# pitch_pause_led.net
KiCad netlist of a schematic drawn in EAGLE
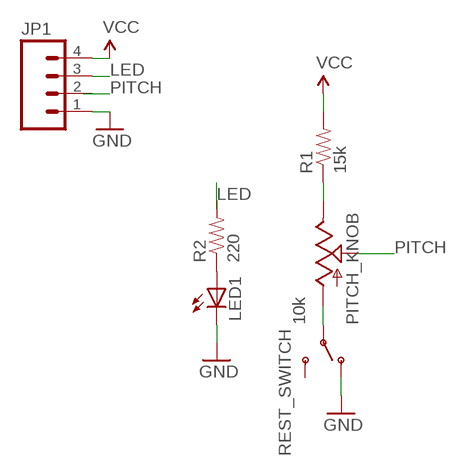
[diagram p0: schematic, sheet 1]

(export (version "E")
  (design (tool "Eeschema 10.0.6"))
  (components
    (comp (ref "JP1")
      (value "M04JST-PTH")
      (footprint "eagle-import:JST-4-PTH")
      (libsource (lib "eagle-import") (part "M04JST-PTH"))
    )
    (comp (ref "LED1")
      (value "LED-3MM-NO_SILK")
      (footprint "eagle-import:LED3MM-NS")
      (libsource (lib "eagle-import") (part "LED-3MM-NO_SILK"))
    )
    (comp (ref "PITCH_KNOB")
      (value "10k")
      (footprint "eagle-import:SPARKFUN_PDB12")
      (libsource (lib "eagle-import") (part "SPARKFUN_POTPDB12"))
    )
    (comp (ref "R1")
      (value "15k")
      (footprint "eagle-import:AXIAL-0.3")
      (libsource (lib "eagle-import") (part "RESISTORAXIAL-0.3"))
    )
    (comp (ref "R2")
      (value "220")
      (footprint "eagle-import:AXIAL-0.3")
      (libsource (lib "eagle-import") (part "RESISTORAXIAL-0.3"))
    )
    (comp (ref "REST_SWITCH")
      (value "SWITCH-SPDTPTH_LOCK")
      (footprint "eagle-import:SWITCH-SPDT_LOCK.007S")
      (libsource (lib "eagle-import") (part "SWITCH-SPDTPTH_LOCK"))
    )
  )
  (nets
    (net (code "1") (name "/LED") (class "Default")
      (node (ref "JP1") (pin "3") (pinfunction "3_3") (pintype "passive"))
      (node (ref "R2") (pin "P$2") (pinfunction "2_P$2") (pintype "passive"))
    )
    (net (code "2") (name "/PITCH") (class "Default")
      (node (ref "PITCH_KNOB") (pin "2") (pinfunction "S_2") (pintype "passive"))
    )
    (net (code "3") (name "GND") (class "Default")
      (node (ref "JP1") (pin "1") (pinfunction "1_1") (pintype "passive"))
      (node (ref "LED1") (pin "K") (pinfunction "C_K") (pintype "passive"))
      (node (ref "REST_SWITCH") (pin "1") (pinfunction "O_1") (pintype "passive"))
    )
    (net (code "4") (name "Net-(PITCH_KNOB-A)") (class "Default")
      (node (ref "PITCH_KNOB") (pin "1") (pinfunction "A_1") (pintype "passive"))
      (node (ref "REST_SWITCH") (pin "2") (pinfunction "P_2") (pintype "passive"))
    )
    (net (code "5") (name "Net-(PITCH_KNOB-E)") (class "Default")
      (node (ref "PITCH_KNOB") (pin "3") (pinfunction "E_3") (pintype "passive"))
      (node (ref "R1") (pin "P$1") (pinfunction "1_P$1") (pintype "passive"))
    )
    (net (code "6") (name "Net-(R2-1)") (class "Default")
      (node (ref "LED1") (pin "A") (pinfunction "A_A") (pintype "passive"))
      (node (ref "R2") (pin "P$1") (pinfunction "1_P$1") (pintype "passive"))
    )
    (net (code "7") (name "VCC") (class "Default")
      (node (ref "JP1") (pin "4") (pinfunction "4_4") (pintype "passive"))
      (node (ref "R1") (pin "P$2") (pinfunction "2_P$2") (pintype "passive"))
    )
    (net (code "8") (name "unconnected-(JP1-Pad2)") (class "Default")
      (node (ref "JP1") (pin "2") (pinfunction "2_2") (pintype "passive"))
    )
    (net (code "9") (name "unconnected-(REST_SWITCH-S-Pad3)") (class "Default")
      (node (ref "REST_SWITCH") (pin "3") (pinfunction "S_3") (pintype "passive"))
    )
  )
)
